# Power.net
KiCad netlist of a schematic drawn in Altium Designer
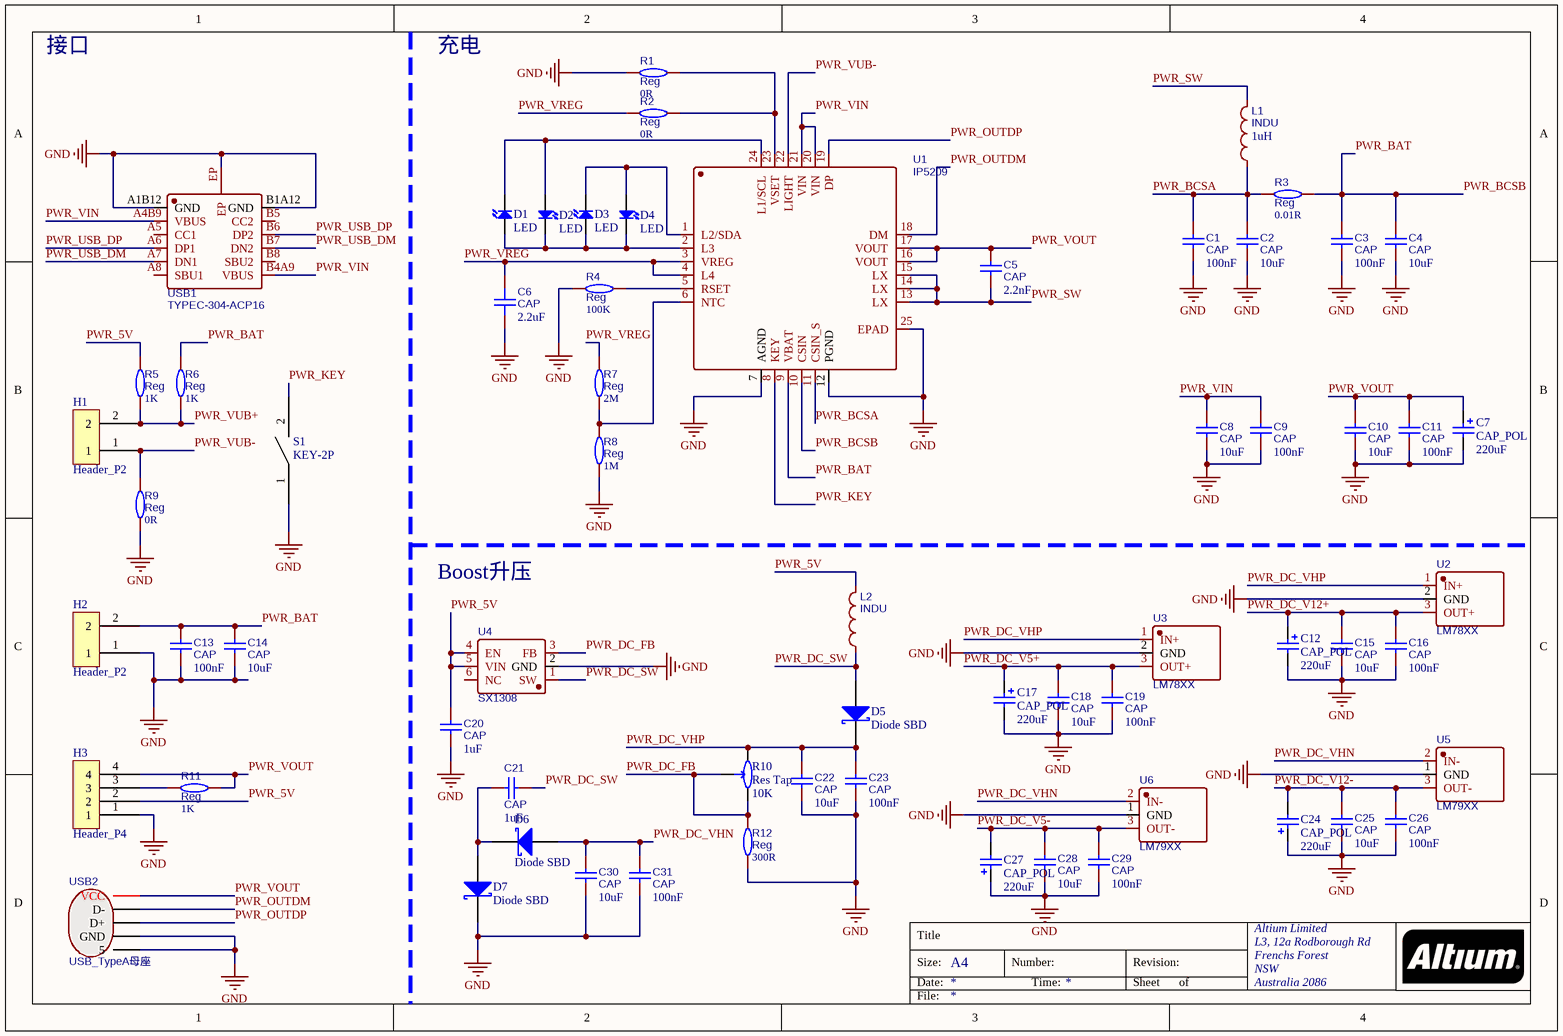
[diagram p0: Power.SchDoc]

(export (version "E")
  (design (tool "Eeschema 10.0.6"))
  (components
    (comp (ref "C1")
      (value "CAP")
      (footprint "C0603")
      (description "Cap")
      (fields
        (field (name "BOM_SUPPLIER PART") "C302008")
        (field (name "BOM_MANUFACTURER PART") "0603B103K101CT")
        (field (name "ALTIUM_VALUE") "100nF")
        (field (name "CONTRIBUTOR") "LCSC")
      )
      (libsource (lib "Levent_lib") (part "CAP"))
    )
    (comp (ref "C2")
      (value "CAP")
      (footprint "C0603")
      (description "Cap")
      (fields
        (field (name "BOM_SUPPLIER PART") "C302008")
        (field (name "BOM_MANUFACTURER PART") "0603B103K101CT")
        (field (name "ALTIUM_VALUE") "10uF")
        (field (name "CONTRIBUTOR") "LCSC")
      )
      (libsource (lib "Levent_lib") (part "CAP"))
    )
    (comp (ref "C3")
      (value "CAP")
      (footprint "C0603")
      (description "Cap")
      (fields
        (field (name "BOM_SUPPLIER PART") "C302008")
        (field (name "BOM_MANUFACTURER PART") "0603B103K101CT")
        (field (name "ALTIUM_VALUE") "100nF")
        (field (name "CONTRIBUTOR") "LCSC")
      )
      (libsource (lib "Levent_lib") (part "CAP"))
    )
    (comp (ref "C4")
      (value "CAP")
      (footprint "C0603")
      (description "Cap")
      (fields
        (field (name "BOM_SUPPLIER PART") "C302008")
        (field (name "BOM_MANUFACTURER PART") "0603B103K101CT")
        (field (name "ALTIUM_VALUE") "10uF")
        (field (name "CONTRIBUTOR") "LCSC")
      )
      (libsource (lib "Levent_lib") (part "CAP"))
    )
    (comp (ref "C5")
      (value "CAP")
      (footprint "C0603")
      (description "Cap")
      (fields
        (field (name "BOM_SUPPLIER PART") "C302008")
        (field (name "BOM_MANUFACTURER PART") "0603B103K101CT")
        (field (name "ALTIUM_VALUE") "2.2nF")
        (field (name "CONTRIBUTOR") "LCSC")
      )
      (libsource (lib "Levent_lib") (part "CAP"))
    )
    (comp (ref "C6")
      (value "CAP")
      (footprint "C0603")
      (description "Cap")
      (fields
        (field (name "BOM_SUPPLIER PART") "C302008")
        (field (name "BOM_MANUFACTURER PART") "0603B103K101CT")
        (field (name "ALTIUM_VALUE") "2.2uF")
        (field (name "CONTRIBUTOR") "LCSC")
      )
      (libsource (lib "") (part "CAP_1"))
    )
    (comp (ref "C7")
      (value "CAP_POL")
      (footprint "CAP_SMD_6.3mm")
      (description "极性电容")
      (fields (field (name "ALTIUM_VALUE") "220uF"))
      (libsource (lib "Levent_lib") (part "CAP_POL"))
    )
    (comp (ref "C8")
      (value "CAP")
      (footprint "C0603")
      (description "Cap")
      (fields
        (field (name "BOM_SUPPLIER PART") "C302008")
        (field (name "BOM_MANUFACTURER PART") "0603B103K101CT")
        (field (name "ALTIUM_VALUE") "10uF")
        (field (name "CONTRIBUTOR") "LCSC")
      )
      (libsource (lib "Levent_lib") (part "CAP"))
    )
    (comp (ref "C9")
      (value "CAP")
      (footprint "C0603")
      (description "Cap")
      (fields
        (field (name "BOM_SUPPLIER PART") "C302008")
        (field (name "BOM_MANUFACTURER PART") "0603B103K101CT")
        (field (name "ALTIUM_VALUE") "100nF")
        (field (name "CONTRIBUTOR") "LCSC")
      )
      (libsource (lib "Levent_lib") (part "CAP"))
    )
    (comp (ref "C10")
      (value "CAP")
      (footprint "C0603")
      (description "Cap")
      (fields
        (field (name "BOM_SUPPLIER PART") "C302008")
        (field (name "BOM_MANUFACTURER PART") "0603B103K101CT")
        (field (name "ALTIUM_VALUE") "10uF")
        (field (name "CONTRIBUTOR") "LCSC")
      )
      (libsource (lib "Levent_lib") (part "CAP"))
    )
    (comp (ref "C11")
      (value "CAP")
      (footprint "C0603")
      (description "Cap")
      (fields
        (field (name "BOM_SUPPLIER PART") "C302008")
        (field (name "BOM_MANUFACTURER PART") "0603B103K101CT")
        (field (name "ALTIUM_VALUE") "100nF")
        (field (name "CONTRIBUTOR") "LCSC")
      )
      (libsource (lib "Levent_lib") (part "CAP"))
    )
    (comp (ref "C12")
      (value "CAP_POL")
      (footprint "CAP_SMD_6.3mm")
      (description "极性电容")
      (fields (field (name "ALTIUM_VALUE") "220uF"))
      (libsource (lib "Levent_lib") (part "CAP_POL"))
    )
    (comp (ref "C13")
      (value "CAP")
      (footprint "C0603")
      (description "Cap")
      (fields
        (field (name "BOM_SUPPLIER PART") "C302008")
        (field (name "BOM_MANUFACTURER PART") "0603B103K101CT")
        (field (name "ALTIUM_VALUE") "100nF")
        (field (name "CONTRIBUTOR") "LCSC")
      )
      (libsource (lib "Levent_lib") (part "CAP"))
    )
    (comp (ref "C14")
      (value "CAP")
      (footprint "C0603")
      (description "Cap")
      (fields
        (field (name "BOM_SUPPLIER PART") "C302008")
        (field (name "BOM_MANUFACTURER PART") "0603B103K101CT")
        (field (name "ALTIUM_VALUE") "10uF")
        (field (name "CONTRIBUTOR") "LCSC")
      )
      (libsource (lib "Levent_lib") (part "CAP"))
    )
    (comp (ref "C15")
      (value "CAP")
      (footprint "C0603")
      (description "Cap")
      (fields
        (field (name "BOM_SUPPLIER PART") "C302008")
        (field (name "BOM_MANUFACTURER PART") "0603B103K101CT")
        (field (name "ALTIUM_VALUE") "10uF")
        (field (name "CONTRIBUTOR") "LCSC")
      )
      (libsource (lib "Levent_lib") (part "CAP"))
    )
    (comp (ref "C16")
      (value "CAP")
      (footprint "C0603")
      (description "Cap")
      (fields
        (field (name "BOM_SUPPLIER PART") "C302008")
        (field (name "BOM_MANUFACTURER PART") "0603B103K101CT")
        (field (name "ALTIUM_VALUE") "100nF")
        (field (name "CONTRIBUTOR") "LCSC")
      )
      (libsource (lib "Levent_lib") (part "CAP"))
    )
    (comp (ref "C17")
      (value "CAP_POL")
      (footprint "CAP_SMD_6.3mm")
      (description "极性电容")
      (fields (field (name "ALTIUM_VALUE") "220uF"))
      (libsource (lib "Levent_lib") (part "CAP_POL"))
    )
    (comp (ref "C18")
      (value "CAP")
      (footprint "C0603")
      (description "Cap")
      (fields
        (field (name "BOM_SUPPLIER PART") "C302008")
        (field (name "BOM_MANUFACTURER PART") "0603B103K101CT")
        (field (name "ALTIUM_VALUE") "10uF")
        (field (name "CONTRIBUTOR") "LCSC")
      )
      (libsource (lib "Levent_lib") (part "CAP"))
    )
    (comp (ref "C19")
      (value "CAP")
      (footprint "C0603")
      (description "Cap")
      (fields
        (field (name "BOM_SUPPLIER PART") "C302008")
        (field (name "BOM_MANUFACTURER PART") "0603B103K101CT")
        (field (name "ALTIUM_VALUE") "100nF")
        (field (name "CONTRIBUTOR") "LCSC")
      )
      (libsource (lib "Levent_lib") (part "CAP"))
    )
    (comp (ref "C20")
      (value "CAP")
      (footprint "C0603")
      (description "Cap")
      (fields
        (field (name "BOM_SUPPLIER PART") "C302008")
        (field (name "BOM_MANUFACTURER PART") "0603B103K101CT")
        (field (name "ALTIUM_VALUE") "1uF")
        (field (name "CONTRIBUTOR") "LCSC")
      )
      (libsource (lib "Levent_lib") (part "CAP"))
    )
    (comp (ref "C21")
      (value "CAP")
      (footprint "C0603")
      (description "Cap")
      (fields
        (field (name "BOM_SUPPLIER PART") "C302008")
        (field (name "BOM_MANUFACTURER PART") "0603B103K101CT")
        (field (name "ALTIUM_VALUE") "1uF")
        (field (name "CONTRIBUTOR") "LCSC")
      )
      (libsource (lib "Levent_lib") (part "CAP"))
    )
    (comp (ref "C22")
      (value "CAP")
      (footprint "C0603")
      (description "Cap")
      (fields
        (field (name "BOM_SUPPLIER PART") "C302008")
        (field (name "BOM_MANUFACTURER PART") "0603B103K101CT")
        (field (name "ALTIUM_VALUE") "10uF")
        (field (name "CONTRIBUTOR") "LCSC")
      )
      (libsource (lib "Levent_lib") (part "CAP"))
    )
    (comp (ref "C23")
      (value "CAP")
      (footprint "C0603")
      (description "Cap")
      (fields
        (field (name "BOM_SUPPLIER PART") "C302008")
        (field (name "BOM_MANUFACTURER PART") "0603B103K101CT")
        (field (name "ALTIUM_VALUE") "100nF")
        (field (name "CONTRIBUTOR") "LCSC")
      )
      (libsource (lib "Levent_lib") (part "CAP"))
    )
    (comp (ref "C24")
      (value "CAP_POL")
      (footprint "CAP_SMD_6.3mm")
      (description "极性电容")
      (fields (field (name "ALTIUM_VALUE") "220uF"))
      (libsource (lib "Levent_lib") (part "CAP_POL"))
    )
    (comp (ref "C25")
      (value "CAP")
      (footprint "C0603")
      (description "Cap")
      (fields
        (field (name "BOM_SUPPLIER PART") "C302008")
        (field (name "BOM_MANUFACTURER PART") "0603B103K101CT")
        (field (name "ALTIUM_VALUE") "10uF")
        (field (name "CONTRIBUTOR") "LCSC")
      )
      (libsource (lib "Levent_lib") (part "CAP"))
    )
    (comp (ref "C26")
      (value "CAP")
      (footprint "C0603")
      (description "Cap")
      (fields
        (field (name "BOM_SUPPLIER PART") "C302008")
        (field (name "BOM_MANUFACTURER PART") "0603B103K101CT")
        (field (name "ALTIUM_VALUE") "100nF")
        (field (name "CONTRIBUTOR") "LCSC")
      )
      (libsource (lib "Levent_lib") (part "CAP"))
    )
    (comp (ref "C27")
      (value "CAP_POL")
      (footprint "CAP_SMD_6.3mm")
      (description "极性电容")
      (fields (field (name "ALTIUM_VALUE") "220uF"))
      (libsource (lib "Levent_lib") (part "CAP_POL"))
    )
    (comp (ref "C28")
      (value "CAP")
      (footprint "C0603")
      (description "Cap")
      (fields
        (field (name "BOM_SUPPLIER PART") "C302008")
        (field (name "BOM_MANUFACTURER PART") "0603B103K101CT")
        (field (name "ALTIUM_VALUE") "10uF")
        (field (name "CONTRIBUTOR") "LCSC")
      )
      (libsource (lib "Levent_lib") (part "CAP"))
    )
    (comp (ref "C29")
      (value "CAP")
      (footprint "C0603")
      (description "Cap")
      (fields
        (field (name "BOM_SUPPLIER PART") "C302008")
        (field (name "BOM_MANUFACTURER PART") "0603B103K101CT")
        (field (name "ALTIUM_VALUE") "100nF")
        (field (name "CONTRIBUTOR") "LCSC")
      )
      (libsource (lib "Levent_lib") (part "CAP"))
    )
    (comp (ref "C30")
      (value "CAP")
      (footprint "C0603")
      (description "Cap")
      (fields
        (field (name "BOM_SUPPLIER PART") "C302008")
        (field (name "BOM_MANUFACTURER PART") "0603B103K101CT")
        (field (name "ALTIUM_VALUE") "10uF")
        (field (name "CONTRIBUTOR") "LCSC")
      )
      (libsource (lib "Levent_lib") (part "CAP"))
    )
    (comp (ref "C31")
      (value "CAP")
      (footprint "C0603")
      (description "Cap")
      (fields
        (field (name "BOM_SUPPLIER PART") "C302008")
        (field (name "BOM_MANUFACTURER PART") "0603B103K101CT")
        (field (name "ALTIUM_VALUE") "100nF")
        (field (name "CONTRIBUTOR") "LCSC")
      )
      (libsource (lib "Levent_lib") (part "CAP"))
    )
    (comp (ref "D1")
      (value "LED")
      (footprint "LED0603_Side")
      (fields (field (name "PUBLISHER") "Altium Limited"))
      (libsource (lib "Levent_lib") (part "LED0"))
    )
    (comp (ref "D2")
      (value "LED")
      (footprint "LED0603_Side")
      (fields (field (name "PUBLISHER") "Altium Limited"))
      (libsource (lib "Levent_lib") (part "LED0"))
    )
    (comp (ref "D3")
      (value "LED")
      (footprint "LED0603_Side")
      (fields (field (name "PUBLISHER") "Altium Limited"))
      (libsource (lib "Levent_lib") (part "LED0"))
    )
    (comp (ref "D4")
      (value "LED")
      (footprint "LED0603_Side")
      (fields (field (name "PUBLISHER") "Altium Limited"))
      (libsource (lib "Levent_lib") (part "LED0"))
    )
    (comp (ref "D5")
      (value "Diode SBD")
      (footprint "SMA_L4.3")
      (description "Schottky Rectifier")
      (fields (field (name "PUBLISHER") "Altium Limited"))
      (libsource (lib "Levent_lib") (part "Diode SBD"))
    )
    (comp (ref "D6")
      (value "Diode SBD")
      (footprint "SMA_L4.3")
      (description "Schottky Rectifier")
      (fields (field (name "PUBLISHER") "Altium Limited"))
      (libsource (lib "Levent_lib") (part "Diode SBD"))
    )
    (comp (ref "D7")
      (value "Diode SBD")
      (footprint "SMA_L4.3")
      (description "Schottky Rectifier")
      (fields (field (name "PUBLISHER") "Altium Limited"))
      (libsource (lib "Levent_lib") (part "Diode SBD"))
    )
    (comp (ref "H1")
      (value "Header_P2")
      (footprint "H_2.54_P2")
      (description "2Pin排针")
      (libsource (lib "Levent_lib") (part "Header_P2"))
    )
    (comp (ref "H2")
      (value "Header_P2")
      (footprint "H_2.54_P2")
      (description "2Pin排针")
      (libsource (lib "Levent_lib") (part "Header_P2"))
    )
    (comp (ref "H3")
      (value "Header_P4")
      (footprint "H_2.54_P4")
      (description "4Pin排针")
      (libsource (lib "Levent_lib") (part "Header_P4"))
    )
    (comp (ref "L1")
      (value "INDU")
      (footprint "SMD_L7.1")
      (description "电感")
      (fields
        (field (name "BOM_SUPPLIER PART") "C182182")
        (field (name "BOM_MANUFACTURER PART") "SLO0630H150MTT")
        (field (name "ALTIUM_VALUE") "1uH")
        (field (name "CONTRIBUTOR") "LCSC")
      )
      (libsource (lib "Levent_lib") (part "IND"))
    )
    (comp (ref "L2")
      (value "INDU")
      (footprint "SMD_L7.1")
      (description "电感")
      (fields
        (field (name "BOM_SUPPLIER PART") "C182182")
        (field (name "BOM_MANUFACTURER PART") "SLO0630H150MTT")
        (field (name "CONTRIBUTOR") "LCSC")
      )
      (libsource (lib "Levent_lib") (part "IND"))
    )
    (comp (ref "R1")
      (value "Reg")
      (footprint "R0603")
      (description "电阻")
      (fields
        (field (name "BOM_SUPPLIER PART") "C465721")
        (field (name "BOM_MANUFACTURER PART") "AR03BTCX1002A")
        (field (name "ALTIUM_VALUE") "0R")
        (field (name "CONTRIBUTOR") "LCSC")
      )
      (libsource (lib "Levent_lib") (part "Res"))
    )
    (comp (ref "R2")
      (value "Reg")
      (footprint "R0603")
      (description "电阻")
      (fields
        (field (name "BOM_SUPPLIER PART") "C465721")
        (field (name "BOM_MANUFACTURER PART") "AR03BTCX1002A")
        (field (name "ALTIUM_VALUE") "0R")
        (field (name "CONTRIBUTOR") "LCSC")
      )
      (libsource (lib "Levent_lib") (part "Res"))
    )
    (comp (ref "R3")
      (value "Reg")
      (footprint "R1206")
      (description "电阻")
      (fields
        (field (name "BOM_SUPPLIER PART") "C465721")
        (field (name "BOM_MANUFACTURER PART") "AR03BTCX1002A")
        (field (name "ALTIUM_VALUE") "0.01R")
        (field (name "CONTRIBUTOR") "LCSC")
      )
      (libsource (lib "Levent_lib") (part "Res"))
    )
    (comp (ref "R4")
      (value "Reg")
      (footprint "R0603")
      (description "电阻")
      (fields
        (field (name "BOM_SUPPLIER PART") "C465721")
        (field (name "BOM_MANUFACTURER PART") "AR03BTCX1002A")
        (field (name "ALTIUM_VALUE") "100K")
        (field (name "CONTRIBUTOR") "LCSC")
      )
      (libsource (lib "Levent_lib") (part "Res"))
    )
    (comp (ref "R5")
      (value "Reg")
      (footprint "R0603")
      (description "电阻")
      (fields
        (field (name "BOM_SUPPLIER PART") "C465721")
        (field (name "BOM_MANUFACTURER PART") "AR03BTCX1002A")
        (field (name "ALTIUM_VALUE") "1K")
        (field (name "CONTRIBUTOR") "LCSC")
      )
      (libsource (lib "Levent_lib") (part "Res"))
    )
    (comp (ref "R6")
      (value "Reg")
      (footprint "R0603")
      (description "电阻")
      (fields
        (field (name "BOM_SUPPLIER PART") "C465721")
        (field (name "BOM_MANUFACTURER PART") "AR03BTCX1002A")
        (field (name "ALTIUM_VALUE") "1K")
        (field (name "CONTRIBUTOR") "LCSC")
      )
      (libsource (lib "Levent_lib") (part "Res"))
    )
    (comp (ref "R7")
      (value "Reg")
      (footprint "R0603")
      (description "电阻")
      (fields
        (field (name "BOM_SUPPLIER PART") "C465721")
        (field (name "BOM_MANUFACTURER PART") "AR03BTCX1002A")
        (field (name "ALTIUM_VALUE") "2M")
        (field (name "CONTRIBUTOR") "LCSC")
      )
      (libsource (lib "Levent_lib") (part "Res"))
    )
    (comp (ref "R8")
      (value "Reg")
      (footprint "R0603")
      (description "电阻")
      (fields
        (field (name "BOM_SUPPLIER PART") "C465721")
        (field (name "BOM_MANUFACTURER PART") "AR03BTCX1002A")
        (field (name "ALTIUM_VALUE") "1M")
        (field (name "CONTRIBUTOR") "LCSC")
      )
      (libsource (lib "Levent_lib") (part "Res"))
    )
    (comp (ref "R9")
      (value "Reg")
      (footprint "R0603")
      (description "电阻")
      (fields
        (field (name "BOM_SUPPLIER PART") "C465721")
        (field (name "BOM_MANUFACTURER PART") "AR03BTCX1002A")
        (field (name "ALTIUM_VALUE") "0R")
        (field (name "CONTRIBUTOR") "LCSC")
      )
      (libsource (lib "Levent_lib") (part "Res"))
    )
    (comp (ref "R10")
      (value "Res Tap")
      (footprint "RES_TAP_HOR")
      (description "可调电阻")
      (fields (field (name "ALTIUM_VALUE") "10K") (field (name "PUBLISHER") "Altium Limited"))
      (libsource (lib "Levent_lib") (part "Res Tap"))
    )
    (comp (ref "R11")
      (value "Reg")
      (footprint "R0603")
      (description "电阻")
      (fields
        (field (name "BOM_SUPPLIER PART") "C465721")
        (field (name "BOM_MANUFACTURER PART") "AR03BTCX1002A")
        (field (name "ALTIUM_VALUE") "1K")
        (field (name "CONTRIBUTOR") "LCSC")
      )
      (libsource (lib "Levent_lib") (part "Res"))
    )
    (comp (ref "R12")
      (value "Reg")
      (footprint "R0603")
      (description "电阻")
      (fields
        (field (name "BOM_SUPPLIER PART") "C465721")
        (field (name "BOM_MANUFACTURER PART") "AR03BTCX1002A")
        (field (name "ALTIUM_VALUE") "300R")
        (field (name "CONTRIBUTOR") "LCSC")
      )
      (libsource (lib "Levent_lib") (part "Res"))
    )
    (comp (ref "S1")
      (value "KEY-2P")
      (footprint "KEY_SOT_P2")
      (description "KEY-2Pp")
      (libsource (lib "Levent_lib") (part "KEY_2P"))
    )
    (comp (ref "U1")
      (value "IP5209")
      (footprint "QFN-24")
      (description "USB充电宝")
      (fields (field (name "BOM_SUPPLIER PART") "C181695") (field (name "CONTRIBUTOR") "LCSC"))
      (libsource (lib "Levent_lib") (part "IP5209"))
    )
    (comp (ref "U2")
      (value "LM78XX")
      (footprint "TO-220-3_2.54_HOR")
      (description "三端稳压(正电压)")
      (fields
        (field (name "BOM_SUPPLIER PART") "C2902509")
        (field (name "BOM_MANUFACTURER PART") "LM7812T")
        (field (name "CONTRIBUTOR") "LCSC")
      )
      (libsource (lib "Levent_lib") (part "LM78XX"))
    )
    (comp (ref "U3")
      (value "LM78XX")
      (footprint "TO-220-3_2.54_HOR")
      (description "三端稳压(正电压)")
      (fields
        (field (name "BOM_SUPPLIER PART") "C2902509")
        (field (name "BOM_MANUFACTURER PART") "LM7812T")
        (field (name "CONTRIBUTOR") "LCSC")
      )
      (libsource (lib "Levent_lib") (part "LM78XX"))
    )
    (comp (ref "U4")
      (value "SX1308")
      (footprint "SOT-23-6")
      (description "升压PWM")
      (fields (field (name "BOM_SUPPLIER PART") "C78162"))
      (libsource (lib "Levent_lib") (part "SX1308"))
    )
    (comp (ref "U5")
      (value "LM79XX")
      (footprint "TO-220-3_2.54_HOR")
      (description "三端稳压(负电压)")
      (fields
        (field (name "BOM_SUPPLIER PART") "C2902509")
        (field (name "BOM_MANUFACTURER PART") "LM7812T")
        (field (name "CONTRIBUTOR") "LCSC")
      )
      (libsource (lib "Levent_lib_commons") (part "LM79XX"))
    )
    (comp (ref "U6")
      (value "LM79XX")
      (footprint "TO-220-3_2.54_HOR")
      (description "三端稳压(负电压)")
      (fields
        (field (name "BOM_SUPPLIER PART") "C2902509")
        (field (name "BOM_MANUFACTURER PART") "LM7812T")
        (field (name "CONTRIBUTOR") "LCSC")
      )
      (libsource (lib "Levent_lib_commons") (part "LM79XX"))
    )
    (comp (ref "USB1")
      (value "TYPEC-304-ACP16")
      (footprint "USB-C-SMD_TYPE-C-16P")
      (description "全引脚USB TYPEC母座")
      (fields (field (name "BOM_SUPPLIER PART") "C2982555") (field (name "CONTRIBUTOR") "LCSC"))
      (libsource (lib "Levent_lib") (part "USB_TYPEC_12P"))
    )
    (comp (ref "USB2")
      (value "USB_TypeA母座")
      (footprint "USB_TYPEA-SMD")
      (fields
        (field (name "BOM_MANUFACTURER PART") "YJ-USB-AF-SMT-01")
        (field (name "BOM_SUPPLIER PART") "C8328")
      )
      (libsource (lib "Levent_lib") (part "USB-TYPEA"))
    )
  )
  (nets
    (net (code "1") (name "/PWR_5V") (class "Default")
      (node (ref "C20") (pin "1") (pinfunction "1_1") (pintype "passive"))
      (node (ref "H3") (pin "2") (pinfunction "2_2") (pintype "passive"))
      (node (ref "L2") (pin "2") (pinfunction "2_2") (pintype "passive"))
      (node (ref "R5") (pin "2") (pinfunction "2_2") (pintype "passive"))
      (node (ref "U4") (pin "4") (pinfunction "EN_4") (pintype "passive"))
      (node (ref "U4") (pin "5") (pinfunction "VIN_5") (pintype "passive"))
    )
    (net (code "2") (name "/PWR_BAT") (class "Default")
      (node (ref "C13") (pin "1") (pinfunction "1_1") (pintype "passive"))
      (node (ref "C14") (pin "1") (pinfunction "1_1") (pintype "passive"))
      (node (ref "C3") (pin "1") (pinfunction "1_1") (pintype "passive"))
      (node (ref "C4") (pin "1") (pinfunction "1_1") (pintype "passive"))
      (node (ref "H2") (pin "2") (pinfunction "2_2") (pintype "passive"))
      (node (ref "R3") (pin "2") (pinfunction "2_2") (pintype "passive"))
      (node (ref "R6") (pin "2") (pinfunction "2_2") (pintype "passive"))
      (node (ref "U1") (pin "10") (pinfunction "CSIN_10") (pintype "passive"))
      (node (ref "U1") (pin "9") (pinfunction "VBAT_9") (pintype "passive"))
    )
    (net (code "3") (name "/PWR_BCSA") (class "Default")
      (node (ref "C1") (pin "1") (pinfunction "1_1") (pintype "passive"))
      (node (ref "C2") (pin "1") (pinfunction "1_1") (pintype "passive"))
      (node (ref "L1") (pin "1") (pinfunction "1_1") (pintype "passive"))
      (node (ref "R3") (pin "1") (pinfunction "1_1") (pintype "passive"))
      (node (ref "U1") (pin "11") (pinfunction "CSIN_S_11") (pintype "passive"))
    )
    (net (code "4") (name "/PWR_DC_FB") (class "Default")
      (node (ref "R10") (pin "1") (pinfunction "A_1") (pintype "passive"))
      (node (ref "R10") (pin "3") (pinfunction "TAP_3") (pintype "passive"))
      (node (ref "R12") (pin "2") (pinfunction "2_2") (pintype "passive"))
      (node (ref "U4") (pin "3") (pinfunction "FB_3") (pintype "passive"))
    )
    (net (code "5") (name "/PWR_DC_SW") (class "Default")
      (node (ref "C21") (pin "1") (pinfunction "1_1") (pintype "passive"))
      (node (ref "D5") (pin "2") (pinfunction "A_2") (pintype "passive"))
      (node (ref "L2") (pin "1") (pinfunction "1_1") (pintype "passive"))
      (node (ref "U4") (pin "1") (pinfunction "SW_1") (pintype "passive"))
    )
    (net (code "6") (name "/PWR_DC_V5+") (class "Default")
      (node (ref "C17") (pin "1") (pinfunction "1_1") (pintype "passive"))
      (node (ref "C18") (pin "1") (pinfunction "1_1") (pintype "passive"))
      (node (ref "C19") (pin "1") (pinfunction "1_1") (pintype "passive"))
      (node (ref "U3") (pin "3") (pinfunction "OUT+_3") (pintype "passive"))
    )
    (net (code "7") (name "/PWR_DC_V5-") (class "Default")
      (node (ref "C27") (pin "2") (pinfunction "2_2") (pintype "passive"))
      (node (ref "C28") (pin "1") (pinfunction "1_1") (pintype "passive"))
      (node (ref "C29") (pin "1") (pinfunction "1_1") (pintype "passive"))
      (node (ref "U6") (pin "3") (pinfunction "OUT-_3") (pintype "passive"))
    )
    (net (code "8") (name "/PWR_DC_V12+") (class "Default")
      (node (ref "C12") (pin "1") (pinfunction "1_1") (pintype "passive"))
      (node (ref "C15") (pin "1") (pinfunction "1_1") (pintype "passive"))
      (node (ref "C16") (pin "1") (pinfunction "1_1") (pintype "passive"))
      (node (ref "U2") (pin "3") (pinfunction "OUT+_3") (pintype "passive"))
    )
    (net (code "9") (name "/PWR_DC_V12-") (class "Default")
      (node (ref "C24") (pin "2") (pinfunction "2_2") (pintype "passive"))
      (node (ref "C25") (pin "1") (pinfunction "1_1") (pintype "passive"))
      (node (ref "C26") (pin "1") (pinfunction "1_1") (pintype "passive"))
      (node (ref "U5") (pin "3") (pinfunction "OUT-_3") (pintype "passive"))
    )
    (net (code "10") (name "/PWR_DC_VHN") (class "Default")
      (node (ref "C30") (pin "1") (pinfunction "1_1") (pintype "passive"))
      (node (ref "C31") (pin "1") (pinfunction "1_1") (pintype "passive"))
      (node (ref "D6") (pin "2") (pinfunction "A_2") (pintype "passive"))
      (node (ref "U5") (pin "2") (pinfunction "IN-_2") (pintype "passive"))
      (node (ref "U6") (pin "2") (pinfunction "IN-_2") (pintype "passive"))
    )
    (net (code "11") (name "/PWR_DC_VHP") (class "Default")
      (node (ref "C22") (pin "1") (pinfunction "1_1") (pintype "passive"))
      (node (ref "C23") (pin "1") (pinfunction "1_1") (pintype "passive"))
      (node (ref "D5") (pin "1") (pinfunction "K_1") (pintype "passive"))
      (node (ref "R10") (pin "2") (pinfunction "B_2") (pintype "passive"))
      (node (ref "U2") (pin "1") (pinfunction "IN+_1") (pintype "passive"))
      (node (ref "U3") (pin "1") (pinfunction "IN+_1") (pintype "passive"))
    )
    (net (code "12") (name "/PWR_KEY") (class "Default")
      (node (ref "S1") (pin "2") (pinfunction "2_2") (pintype "passive"))
      (node (ref "U1") (pin "8") (pinfunction "KEY_8") (pintype "passive"))
    )
    (net (code "13") (name "/PWR_OUTDM") (class "Default")
      (node (ref "U1") (pin "18") (pinfunction "DM_18") (pintype "passive"))
      (node (ref "USB2") (pin "2") (pinfunction "D-_2") (pintype "passive"))
    )
    (net (code "14") (name "/PWR_OUTDP") (class "Default")
      (node (ref "U1") (pin "19") (pinfunction "DP_19") (pintype "passive"))
      (node (ref "USB2") (pin "3") (pinfunction "D+_3") (pintype "passive"))
    )
    (net (code "15") (name "/PWR_SW") (class "Default")
      (node (ref "C5") (pin "2") (pinfunction "2_2") (pintype "passive"))
      (node (ref "L1") (pin "2") (pinfunction "2_2") (pintype "passive"))
      (node (ref "U1") (pin "13") (pinfunction "LX_13") (pintype "passive"))
      (node (ref "U1") (pin "14") (pinfunction "LX_14") (pintype "passive"))
      (node (ref "U1") (pin "15") (pinfunction "LX_15") (pintype "passive"))
    )
    (net (code "16") (name "/PWR_USB_DM") (class "Default")
      (node (ref "USB1") (pin "A7") (pinfunction "DN1_A7") (pintype "passive"))
      (node (ref "USB1") (pin "B7") (pinfunction "DN2_B7") (pintype "passive"))
    )
    (net (code "17") (name "/PWR_USB_DP") (class "Default")
      (node (ref "USB1") (pin "A6") (pinfunction "DP1_A6") (pintype "passive"))
      (node (ref "USB1") (pin "B6") (pinfunction "DP2_B6") (pintype "passive"))
    )
    (net (code "18") (name "/PWR_VIN") (class "Default")
      (node (ref "C8") (pin "1") (pinfunction "1_1") (pintype "passive"))
      (node (ref "C9") (pin "1") (pinfunction "1_1") (pintype "passive"))
      (node (ref "U1") (pin "20") (pinfunction "VIN_20") (pintype "passive"))
      (node (ref "U1") (pin "21") (pinfunction "VIN_21") (pintype "passive"))
      (node (ref "USB1") (pin "A4B9") (pinfunction "VBUS_A4B9") (pintype "passive"))
      (node (ref "USB1") (pin "B4A9") (pinfunction "VBUS_B4A9") (pintype "passive"))
    )
    (net (code "19") (name "/PWR_VOUT") (class "Default")
      (node (ref "C10") (pin "1") (pinfunction "1_1") (pintype "passive"))
      (node (ref "C11") (pin "1") (pinfunction "1_1") (pintype "passive"))
      (node (ref "C5") (pin "1") (pinfunction "1_1") (pintype "passive"))
      (node (ref "C7") (pin "1") (pinfunction "1_1") (pintype "passive"))
      (node (ref "H3") (pin "4") (pinfunction "4_4") (pintype "passive"))
      (node (ref "R11") (pin "1") (pinfunction "1_1") (pintype "passive"))
      (node (ref "U1") (pin "16") (pinfunction "VOUT_16") (pintype "passive"))
      (node (ref "U1") (pin "17") (pinfunction "VOUT_17") (pintype "passive"))
      (node (ref "USB2") (pin "1") (pinfunction "VCC_1") (pintype "passive"))
    )
    (net (code "20") (name "/PWR_VREG") (class "Default")
      (node (ref "C6") (pin "1") (pinfunction "1_1") (pintype "passive"))
      (node (ref "R2") (pin "2") (pinfunction "2_2") (pintype "passive"))
      (node (ref "R7") (pin "1") (pinfunction "1_1") (pintype "passive"))
      (node (ref "U1") (pin "3") (pinfunction "VREG_3") (pintype "passive"))
      (node (ref "U1") (pin "4") (pinfunction "L4_4") (pintype "passive"))
    )
    (net (code "21") (name "/PWR_VUB+") (class "Default")
      (node (ref "H1") (pin "2") (pinfunction "2_2") (pintype "passive"))
      (node (ref "R5") (pin "1") (pinfunction "1_1") (pintype "passive"))
      (node (ref "R6") (pin "1") (pinfunction "1_1") (pintype "passive"))
    )
    (net (code "22") (name "/PWR_VUB-") (class "Default")
      (node (ref "H1") (pin "1") (pinfunction "1_1") (pintype "passive"))
      (node (ref "R9") (pin "2") (pinfunction "2_2") (pintype "passive"))
      (node (ref "U1") (pin "22") (pinfunction "LIGHT_22") (pintype "passive"))
    )
    (net (code "23") (name "GND") (class "Default")
      (node (ref "C1") (pin "2") (pinfunction "2_2") (pintype "passive"))
      (node (ref "C10") (pin "2") (pinfunction "2_2") (pintype "passive"))
      (node (ref "C11") (pin "2") (pinfunction "2_2") (pintype "passive"))
      (node (ref "C12") (pin "2") (pinfunction "2_2") (pintype "passive"))
      (node (ref "C13") (pin "2") (pinfunction "2_2") (pintype "passive"))
      (node (ref "C14") (pin "2") (pinfunction "2_2") (pintype "passive"))
      (node (ref "C15") (pin "2") (pinfunction "2_2") (pintype "passive"))
      (node (ref "C16") (pin "2") (pinfunction "2_2") (pintype "passive"))
      (node (ref "C17") (pin "2") (pinfunction "2_2") (pintype "passive"))
      (node (ref "C18") (pin "2") (pinfunction "2_2") (pintype "passive"))
      (node (ref "C19") (pin "2") (pinfunction "2_2") (pintype "passive"))
      (node (ref "C2") (pin "2") (pinfunction "2_2") (pintype "passive"))
      (node (ref "C20") (pin "2") (pinfunction "2_2") (pintype "passive"))
      (node (ref "C22") (pin "2") (pinfunction "2_2") (pintype "passive"))
      (node (ref "C23") (pin "2") (pinfunction "2_2") (pintype "passive"))
      (node (ref "C24") (pin "1") (pinfunction "1_1") (pintype "passive"))
      (node (ref "C25") (pin "2") (pinfunction "2_2") (pintype "passive"))
      (node (ref "C26") (pin "2") (pinfunction "2_2") (pintype "passive"))
      (node (ref "C27") (pin "1") (pinfunction "1_1") (pintype "passive"))
      (node (ref "C28") (pin "2") (pinfunction "2_2") (pintype "passive"))
      (node (ref "C29") (pin "2") (pinfunction "2_2") (pintype "passive"))
      (node (ref "C3") (pin "2") (pinfunction "2_2") (pintype "passive"))
      (node (ref "C30") (pin "2") (pinfunction "2_2") (pintype "passive"))
      (node (ref "C31") (pin "2") (pinfunction "2_2") (pintype "passive"))
      (node (ref "C4") (pin "2") (pinfunction "2_2") (pintype "passive"))
      (node (ref "C6") (pin "2") (pinfunction "2_2") (pintype "passive"))
      (node (ref "C7") (pin "2") (pinfunction "2_2") (pintype "passive"))
      (node (ref "C8") (pin "2") (pinfunction "2_2") (pintype "passive"))
      (node (ref "C9") (pin "2") (pinfunction "2_2") (pintype "passive"))
      (node (ref "D7") (pin "1") (pinfunction "K_1") (pintype "passive"))
      (node (ref "H2") (pin "1") (pinfunction "1_1") (pintype "passive"))
      (node (ref "H3") (pin "1") (pinfunction "1_1") (pintype "passive"))
      (node (ref "R1") (pin "2") (pinfunction "2_2") (pintype "passive"))
      (node (ref "R12") (pin "1") (pinfunction "1_1") (pintype "passive"))
      (node (ref "R4") (pin "2") (pinfunction "2_2") (pintype "passive"))
      (node (ref "R8") (pin "2") (pinfunction "2_2") (pintype "passive"))
      (node (ref "R9") (pin "1") (pinfunction "1_1") (pintype "passive"))
      (node (ref "S1") (pin "1") (pinfunction "1_1") (pintype "passive"))
      (node (ref "U1") (pin "12") (pinfunction "PGND_12") (pintype "passive"))
      (node (ref "U1") (pin "25") (pinfunction "EPAD_25") (pintype "passive"))
      (node (ref "U1") (pin "7") (pinfunction "AGND_7") (pintype "passive"))
      (node (ref "U2") (pin "2") (pinfunction "GND_2") (pintype "passive"))
      (node (ref "U3") (pin "2") (pinfunction "GND_2") (pintype "passive"))
      (node (ref "U4") (pin "2") (pinfunction "GND_2") (pintype "passive"))
      (node (ref "U5") (pin "1") (pinfunction "GND_1") (pintype "passive"))
      (node (ref "U6") (pin "1") (pinfunction "GND_1") (pintype "passive"))
      (node (ref "USB1") (pin "A1B12") (pinfunction "GND_A1B12") (pintype "passive"))
      (node (ref "USB1") (pin "B1A12") (pinfunction "GND_B1A12") (pintype "passive"))
      (node (ref "USB1") (pin "EP") (pinfunction "EP_EP") (pintype "passive"))
      (node (ref "USB2") (pin "4") (pinfunction "GND_4") (pintype "passive"))
      (node (ref "USB2") (pin "5") (pinfunction "5_5") (pintype "passive"))
    )
    (net (code "24") (name "Net-(D1-A)") (class "Default")
      (node (ref "D1") (pin "2") (pinfunction "A_2") (pintype "passive"))
      (node (ref "D2") (pin "1") (pinfunction "K_1") (pintype "passive"))
      (node (ref "D3") (pin "2") (pinfunction "A_2") (pintype "passive"))
      (node (ref "D4") (pin "1") (pinfunction "K_1") (pintype "passive"))
      (node (ref "U1") (pin "2") (pinfunction "L3_2") (pintype "passive"))
    )
    (net (code "25") (name "Net-(D1-K)") (class "Default")
      (node (ref "D1") (pin "1") (pinfunction "K_1") (pintype "passive"))
      (node (ref "D2") (pin "2") (pinfunction "A_2") (pintype "passive"))
      (node (ref "U1") (pin "24") (pinfunction "L1/SCL_24") (pintype "passive"))
    )
    (net (code "26") (name "Net-(D3-K)") (class "Default")
      (node (ref "D3") (pin "1") (pinfunction "K_1") (pintype "passive"))
      (node (ref "D4") (pin "2") (pinfunction "A_2") (pintype "passive"))
      (node (ref "U1") (pin "1") (pinfunction "L2/SDA_1") (pintype "passive"))
    )
    (net (code "27") (name "Net-(D6-K)") (class "Default")
      (node (ref "C21") (pin "2") (pinfunction "2_2") (pintype "passive"))
      (node (ref "D6") (pin "1") (pinfunction "K_1") (pintype "passive"))
      (node (ref "D7") (pin "2") (pinfunction "A_2") (pintype "passive"))
    )
    (net (code "28") (name "Net-(H3-Pad3)") (class "Default")
      (node (ref "H3") (pin "3") (pinfunction "3_3") (pintype "passive"))
      (node (ref "R11") (pin "2") (pinfunction "2_2") (pintype "passive"))
    )
    (net (code "29") (name "Net-(U1-NTC)") (class "Default")
      (node (ref "R7") (pin "2") (pinfunction "2_2") (pintype "passive"))
      (node (ref "R8") (pin "1") (pinfunction "1_1") (pintype "passive"))
      (node (ref "U1") (pin "6") (pinfunction "NTC_6") (pintype "passive"))
    )
    (net (code "30") (name "Net-(U1-RSET)") (class "Default")
      (node (ref "R4") (pin "1") (pinfunction "1_1") (pintype "passive"))
      (node (ref "U1") (pin "5") (pinfunction "RSET_5") (pintype "passive"))
    )
    (net (code "31") (name "Net-(U1-VSET)") (class "Default")
      (node (ref "R1") (pin "1") (pinfunction "1_1") (pintype "passive"))
      (node (ref "R2") (pin "1") (pinfunction "1_1") (pintype "passive"))
      (node (ref "U1") (pin "23") (pinfunction "VSET_23") (pintype "passive"))
    )
    (net (code "32") (name "unconnected-(U4-NC-Pad6)") (class "Default")
      (node (ref "U4") (pin "6") (pinfunction "NC_6") (pintype "passive"))
    )
    (net (code "33") (name "unconnected-(USB1-CC1-PadA5)") (class "Default")
      (node (ref "USB1") (pin "A5") (pinfunction "CC1_A5") (pintype "passive"))
    )
    (net (code "34") (name "unconnected-(USB1-CC2-PadB5)") (class "Default")
      (node (ref "USB1") (pin "B5") (pinfunction "CC2_B5") (pintype "passive"))
    )
    (net (code "35") (name "unconnected-(USB1-SBU1-PadA8)") (class "Default")
      (node (ref "USB1") (pin "A8") (pinfunction "SBU1_A8") (pintype "passive"))
    )
    (net (code "36") (name "unconnected-(USB1-SBU2-PadB8)") (class "Default")
      (node (ref "USB1") (pin "B8") (pinfunction "SBU2_B8") (pintype "passive"))
    )
  )
)
